# untitled.net
KiCad netlist of a schematic drawn in EAGLE
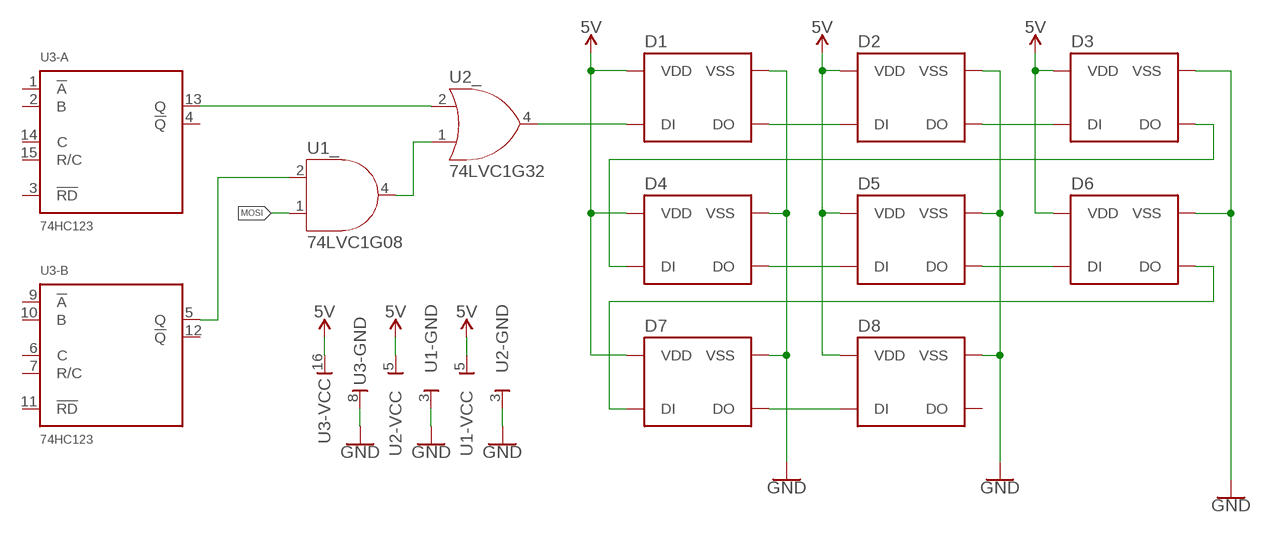
[diagram p0: schematic, sheet 1]

(export (version "E")
  (design (tool "Eeschema 10.0.6"))
  (components
    (comp (ref "D1")
      (value "WS2812B3535")
      (footprint "eagle-import:3535")
      (libsource (lib "eagle-import") (part "WS2812B3535"))
    )
    (comp (ref "D2")
      (value "WS2812B3535")
      (footprint "eagle-import:3535")
      (libsource (lib "eagle-import") (part "WS2812B3535"))
    )
    (comp (ref "D3")
      (value "WS2812B3535")
      (footprint "eagle-import:3535")
      (libsource (lib "eagle-import") (part "WS2812B3535"))
    )
    (comp (ref "D4")
      (value "WS2812B3535")
      (footprint "eagle-import:3535")
      (libsource (lib "eagle-import") (part "WS2812B3535"))
    )
    (comp (ref "D5")
      (value "WS2812B3535")
      (footprint "eagle-import:3535")
      (libsource (lib "eagle-import") (part "WS2812B3535"))
    )
    (comp (ref "D6")
      (value "WS2812B3535")
      (footprint "eagle-import:3535")
      (libsource (lib "eagle-import") (part "WS2812B3535"))
    )
    (comp (ref "D7")
      (value "WS2812B3535")
      (footprint "eagle-import:3535")
      (libsource (lib "eagle-import") (part "WS2812B3535"))
    )
    (comp (ref "D8")
      (value "WS2812B3535")
      (footprint "eagle-import:3535")
      (libsource (lib "eagle-import") (part "WS2812B3535"))
    )
    (comp (ref "U1")
      (value "74LVC1G08")
      (footprint "eagle-import:SC-70-5")
      (libsource (lib "eagle-import") (part "74LVC1G08"))
    )
    (comp (ref "U2")
      (value "74LVC1G32")
      (footprint "eagle-import:SC-70-5")
      (libsource (lib "eagle-import") (part "74LVC1G32"))
    )
    (comp (ref "U3")
      (value "74HC123")
      (footprint "eagle-import:TSSOP-16")
      (libsource (lib "eagle-import") (part "74HC123"))
    )
  )
  (nets
    (net (code "1") (name "5V") (class "Default")
      (node (ref "D1") (pin "2") (pinfunction "VDD_2") (pintype "bidirectional"))
      (node (ref "D2") (pin "2") (pinfunction "VDD_2") (pintype "bidirectional"))
      (node (ref "D3") (pin "2") (pinfunction "VDD_2") (pintype "bidirectional"))
      (node (ref "D4") (pin "2") (pinfunction "VDD_2") (pintype "bidirectional"))
      (node (ref "D5") (pin "2") (pinfunction "VDD_2") (pintype "bidirectional"))
      (node (ref "D6") (pin "2") (pinfunction "VDD_2") (pintype "bidirectional"))
      (node (ref "D7") (pin "2") (pinfunction "VDD_2") (pintype "bidirectional"))
      (node (ref "D8") (pin "2") (pinfunction "VDD_2") (pintype "bidirectional"))
      (node (ref "U1") (pin "5") (pinfunction "P$1_5") (pintype "bidirectional"))
      (node (ref "U2") (pin "5") (pinfunction "P$1_5") (pintype "bidirectional"))
      (node (ref "U3") (pin "16") (pinfunction "P$1_16") (pintype "bidirectional"))
    )
    (net (code "2") (name "GND") (class "Default")
      (node (ref "D1") (pin "4") (pinfunction "VSS_4") (pintype "bidirectional"))
      (node (ref "D2") (pin "4") (pinfunction "VSS_4") (pintype "bidirectional"))
      (node (ref "D3") (pin "4") (pinfunction "VSS_4") (pintype "bidirectional"))
      (node (ref "D4") (pin "4") (pinfunction "VSS_4") (pintype "bidirectional"))
      (node (ref "D5") (pin "4") (pinfunction "VSS_4") (pintype "bidirectional"))
      (node (ref "D6") (pin "4") (pinfunction "VSS_4") (pintype "bidirectional"))
      (node (ref "D7") (pin "4") (pinfunction "VSS_4") (pintype "bidirectional"))
      (node (ref "D8") (pin "4") (pinfunction "VSS_4") (pintype "bidirectional"))
      (node (ref "U1") (pin "3") (pinfunction "P$1_3") (pintype "bidirectional"))
      (node (ref "U2") (pin "3") (pinfunction "P$1_3") (pintype "bidirectional"))
      (node (ref "U3") (pin "8") (pinfunction "P$1_8") (pintype "bidirectional"))
    )
    (net (code "3") (name "MOSI") (class "Default")
      (node (ref "U1") (pin "1") (pinfunction "B_1") (pintype "input"))
    )
    (net (code "4") (name "Net-(D1-DI)") (class "Default")
      (node (ref "D1") (pin "1") (pinfunction "DI_1") (pintype "bidirectional"))
      (node (ref "U2") (pin "4") (pinfunction "Y_4") (pintype "output"))
    )
    (net (code "5") (name "Net-(D1-DO)") (class "Default")
      (node (ref "D1") (pin "3") (pinfunction "DO_3") (pintype "bidirectional"))
      (node (ref "D2") (pin "1") (pinfunction "DI_1") (pintype "bidirectional"))
    )
    (net (code "6") (name "Net-(D2-DO)") (class "Default")
      (node (ref "D2") (pin "3") (pinfunction "DO_3") (pintype "bidirectional"))
      (node (ref "D3") (pin "1") (pinfunction "DI_1") (pintype "bidirectional"))
    )
    (net (code "7") (name "Net-(D3-DO)") (class "Default")
      (node (ref "D3") (pin "3") (pinfunction "DO_3") (pintype "bidirectional"))
      (node (ref "D4") (pin "1") (pinfunction "DI_1") (pintype "bidirectional"))
    )
    (net (code "8") (name "Net-(D4-DO)") (class "Default")
      (node (ref "D4") (pin "3") (pinfunction "DO_3") (pintype "bidirectional"))
      (node (ref "D5") (pin "1") (pinfunction "DI_1") (pintype "bidirectional"))
    )
    (net (code "9") (name "Net-(D5-DO)") (class "Default")
      (node (ref "D5") (pin "3") (pinfunction "DO_3") (pintype "bidirectional"))
      (node (ref "D6") (pin "1") (pinfunction "DI_1") (pintype "bidirectional"))
    )
    (net (code "10") (name "Net-(D6-DO)") (class "Default")
      (node (ref "D6") (pin "3") (pinfunction "DO_3") (pintype "bidirectional"))
      (node (ref "D7") (pin "1") (pinfunction "DI_1") (pintype "bidirectional"))
    )
    (net (code "11") (name "Net-(D7-DO)") (class "Default")
      (node (ref "D7") (pin "3") (pinfunction "DO_3") (pintype "bidirectional"))
      (node (ref "D8") (pin "1") (pinfunction "DI_1") (pintype "bidirectional"))
    )
    (net (code "12") (name "Net-(U1C-A)") (class "Default")
      (node (ref "U1") (pin "2") (pinfunction "A_2") (pintype "input"))
      (node (ref "U3") (pin "5") (pinfunction "Q_5") (pintype "bidirectional"))
    )
    (net (code "13") (name "Net-(U1C-Y)") (class "Default")
      (node (ref "U1") (pin "4") (pinfunction "Y_4") (pintype "output"))
      (node (ref "U2") (pin "1") (pinfunction "B_1") (pintype "input"))
    )
    (net (code "14") (name "Net-(U2C-A)") (class "Default")
      (node (ref "U2") (pin "2") (pinfunction "A_2") (pintype "input"))
      (node (ref "U3") (pin "13") (pinfunction "Q_13") (pintype "bidirectional"))
    )
    (net (code "15") (name "unconnected-(D8-DO-Pad3)") (class "Default")
      (node (ref "D8") (pin "3") (pinfunction "DO_3") (pintype "bidirectional"))
    )
    (net (code "16") (name "unconnected-(U3A-B-Pad2)") (class "Default")
      (node (ref "U3") (pin "2") (pinfunction "B_2") (pintype "bidirectional"))
    )
    (net (code "17") (name "unconnected-(U3A-C-Pad14)") (class "Default")
      (node (ref "U3") (pin "14") (pinfunction "C_14") (pintype "bidirectional"))
    )
    (net (code "18") (name "unconnected-(U3A-R{slash}C-Pad15)") (class "Default")
      (node (ref "U3") (pin "15") (pinfunction "R/C_15") (pintype "bidirectional"))
    )
    (net (code "19") (name "unconnected-(U3A-~{A}-Pad1)") (class "Default")
      (node (ref "U3") (pin "1") (pinfunction "~{A}_1") (pintype "bidirectional"))
    )
    (net (code "20") (name "unconnected-(U3A-~{Q}-Pad4)") (class "Default")
      (node (ref "U3") (pin "4") (pinfunction "~{Q}_4") (pintype "bidirectional"))
    )
    (net (code "21") (name "unconnected-(U3A-~{RD}-Pad3)") (class "Default")
      (node (ref "U3") (pin "3") (pinfunction "~{RD}_3") (pintype "bidirectional"))
    )
    (net (code "22") (name "unconnected-(U3B-B-Pad10)") (class "Default")
      (node (ref "U3") (pin "10") (pinfunction "B_10") (pintype "bidirectional"))
    )
    (net (code "23") (name "unconnected-(U3B-C-Pad6)") (class "Default")
      (node (ref "U3") (pin "6") (pinfunction "C_6") (pintype "bidirectional"))
    )
    (net (code "24") (name "unconnected-(U3B-R{slash}C-Pad7)") (class "Default")
      (node (ref "U3") (pin "7") (pinfunction "R/C_7") (pintype "bidirectional"))
    )
    (net (code "25") (name "unconnected-(U3B-~{A}-Pad9)") (class "Default")
      (node (ref "U3") (pin "9") (pinfunction "~{A}_9") (pintype "bidirectional"))
    )
    (net (code "26") (name "unconnected-(U3B-~{Q}-Pad12)") (class "Default")
      (node (ref "U3") (pin "12") (pinfunction "~{Q}_12") (pintype "bidirectional"))
    )
    (net (code "27") (name "unconnected-(U3B-~{RD}-Pad11)") (class "Default")
      (node (ref "U3") (pin "11") (pinfunction "~{RD}_11") (pintype "bidirectional"))
    )
  )
)
